# STM32F103.net
KiCad netlist of a schematic drawn in Altium Designer
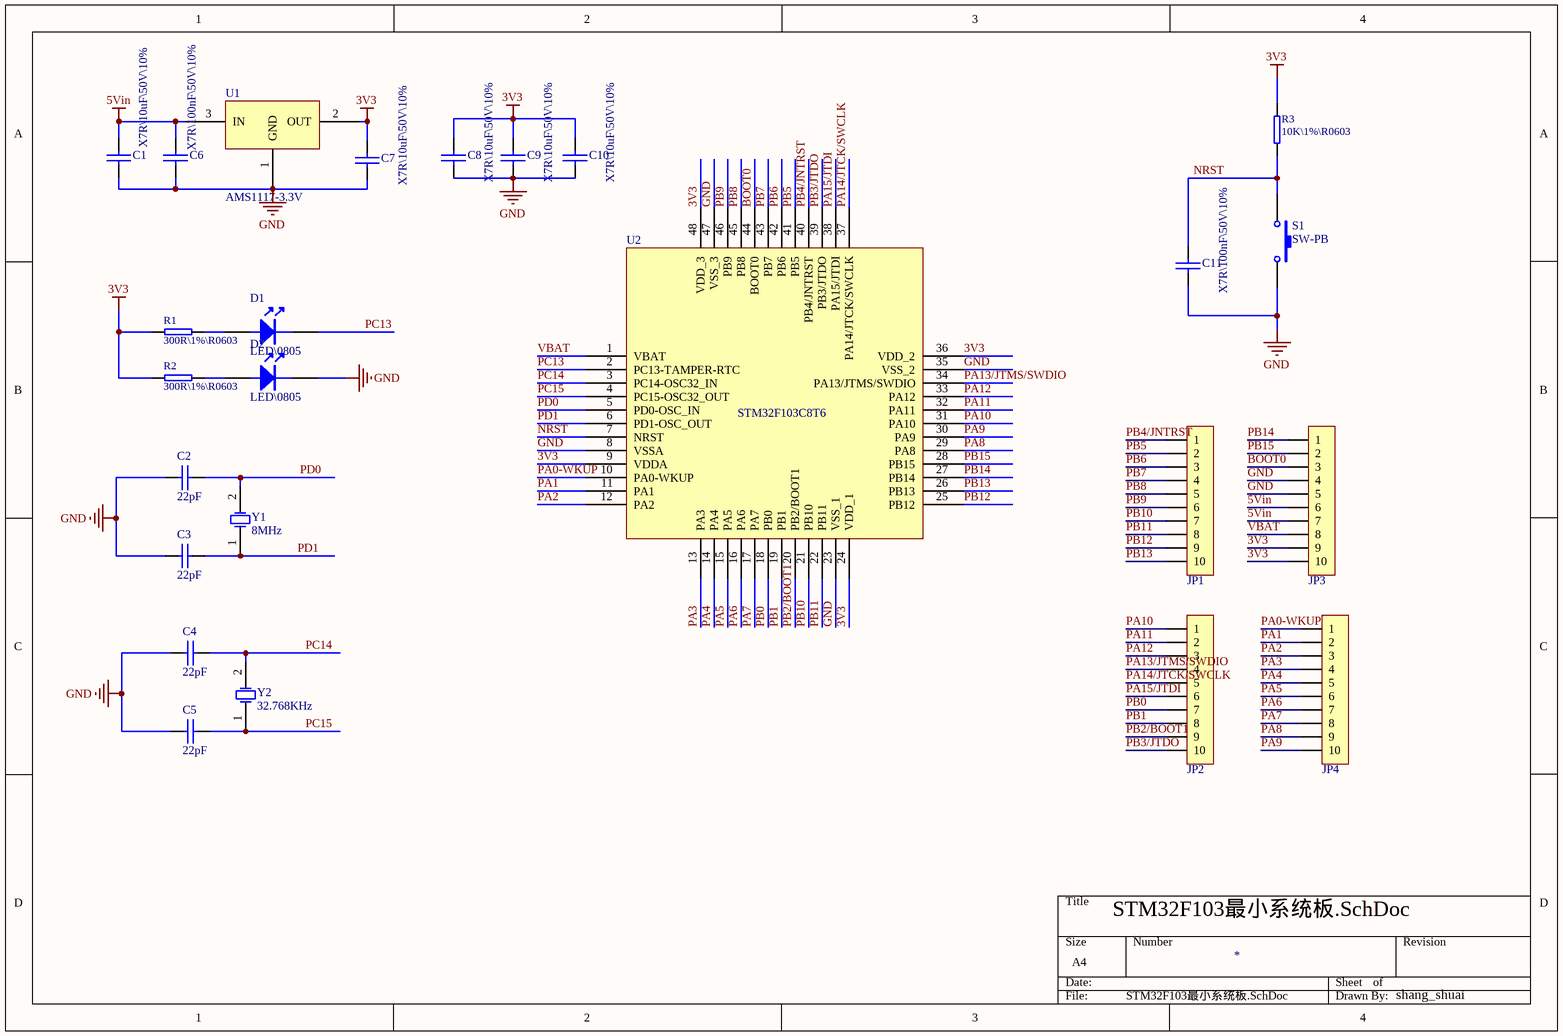
[diagram p0: STM32F103最小系统板.SchDoc]

(export (version "E")
  (design (tool "Eeschema 10.0.6"))
  (components
    (comp (ref "C1")
      (value "X7~{R}10u~{F}50~{V}10%")
      (footprint "C0603")
      (description "Capacitor")
      (libsource (lib "SSSCH") (part "C"))
    )
    (comp (ref "C2")
      (value "22pF")
      (footprint "C0603")
      (description "Capacitor")
      (libsource (lib "SSSCH") (part "C"))
    )
    (comp (ref "C3")
      (value "22pF")
      (footprint "C0603")
      (description "Capacitor")
      (libsource (lib "SSSCH") (part "C"))
    )
    (comp (ref "C4")
      (value "22pF")
      (footprint "C0603")
      (description "Capacitor")
      (libsource (lib "SSSCH") (part "C"))
    )
    (comp (ref "C5")
      (value "22pF")
      (footprint "C0603")
      (description "Capacitor")
      (libsource (lib "SSSCH") (part "C"))
    )
    (comp (ref "C6")
      (value "X7~{R}100n~{F}50~{V}10%")
      (footprint "C0603")
      (description "Capacitor")
      (libsource (lib "SSSCH") (part "C"))
    )
    (comp (ref "C7")
      (value "X7~{R}10u~{F}50~{V}10%")
      (footprint "C0603")
      (description "Capacitor")
      (libsource (lib "SSSCH") (part "C"))
    )
    (comp (ref "C8")
      (value "X7~{R}10u~{F}50~{V}10%")
      (footprint "C0603")
      (description "Capacitor")
      (libsource (lib "SSSCH") (part "C"))
    )
    (comp (ref "C9")
      (value "X7~{R}10u~{F}50~{V}10%")
      (footprint "C0603")
      (description "Capacitor")
      (libsource (lib "SSSCH") (part "C"))
    )
    (comp (ref "C10")
      (value "X7~{R}10u~{F}50~{V}10%")
      (footprint "C0603")
      (description "Capacitor")
      (libsource (lib "SSSCH") (part "C"))
    )
    (comp (ref "C11")
      (value "X7~{R}100n~{F}50~{V}10%")
      (footprint "C0603")
      (description "Capacitor")
      (libsource (lib "SSSCH") (part "C"))
    )
    (comp (ref "D1")
      (value "LE~{D}0805")
      (footprint "LED 0805R")
      (description "红色")
      (libsource (lib "SSSCH") (part "LED"))
    )
    (comp (ref "D2")
      (value "LE~{D}0805")
      (footprint "LED 0805R")
      (description "红色")
      (libsource (lib "SSSCH") (part "LED"))
    )
    (comp (ref "JP1")
      (value "HDR-1X10")
      (footprint "HDR2.54-LI-10P")
      (description "10P接插件")
      (fields (field (name "版权归属") "源创客"))
      (libsource (lib "4.5   - 接插件-脚距2.54") (part "Header 10"))
    )
    (comp (ref "JP2")
      (value "HDR-1X10")
      (footprint "HDR2.54-LI-10P")
      (description "10P接插件")
      (fields (field (name "版权归属") "源创客"))
      (libsource (lib "4.5   - 接插件-脚距2.54") (part "Header 10"))
    )
    (comp (ref "JP3")
      (value "HDR-1X10")
      (footprint "HDR2.54-LI-10P")
      (description "10P接插件")
      (fields (field (name "版权归属") "源创客"))
      (libsource (lib "4.5   - 接插件-脚距2.54") (part "Header 10"))
    )
    (comp (ref "JP4")
      (value "HDR-1X10")
      (footprint "HDR2.54-LI-10P")
      (description "10P接插件")
      (fields (field (name "版权归属") "源创客"))
      (libsource (lib "4.5   - 接插件-脚距2.54") (part "Header 10"))
    )
    (comp (ref "R1")
      (value "300~{R}1~{%}R0603")
      (footprint "R0603")
      (description "电阻")
      (libsource (lib "SSSCH") (part "R"))
    )
    (comp (ref "R2")
      (value "300~{R}1~{%}R0603")
      (footprint "R0603")
      (description "电阻")
      (libsource (lib "SSSCH") (part "R"))
    )
    (comp (ref "R3")
      (value "10~{K}1~{%}R0603")
      (footprint "R0603")
      (description "电阻")
      (libsource (lib "SSSCH") (part "R"))
    )
    (comp (ref "S1")
      (value "SW-PB")
      (footprint "TSW SMD-3*6*4.3")
      (description "Switch")
      (fields (field (name "PUBLISHER") "Altium Limited"))
      (libsource (lib "Miscellaneous Devices") (part "SW-PB"))
    )
    (comp (ref "U1")
      (value "AMS1117-3.3V")
      (footprint "SOT223_L")
      (libsource (lib "SSSCH") (part "AMS1117-3.3V"))
    )
    (comp (ref "U2")
      (value "STM32F103C8T6")
      (footprint "LQFP48-7*7")
      (description "48PIN")
      (libsource (lib "SSSCH") (part "STM32F103C8T6"))
    )
    (comp (ref "Y1")
      (value "8MHz")
      (footprint "OSC HC-49S")
      (description "2脚无源脚晶振")
      (fields (field (name "PUBLISHER") "Altium Limited"))
      (libsource (lib "Miscellaneous Devices") (part "XTAL"))
    )
    (comp (ref "Y2")
      (value "32.768KHz")
      (footprint "OSC-2x6-WI-B")
      (description "2脚无源脚晶振")
      (fields (field (name "PUBLISHER") "Altium Limited"))
      (libsource (lib "Miscellaneous Devices") (part "XTAL"))
    )
  )
  (nets
    (net (code "1") (name "/BOOT0") (class "Default")
      (node (ref "JP3") (pin "3") (pinfunction "3_3") (pintype "passive"))
      (node (ref "U2") (pin "44") (pinfunction "BOOT0_44") (pintype "passive"))
    )
    (net (code "2") (name "/NRST") (class "Default")
      (node (ref "C11") (pin "1") (pintype "passive"))
      (node (ref "R3") (pin "2") (pintype "passive"))
      (node (ref "S1") (pin "1") (pinfunction "1_1") (pintype "passive"))
      (node (ref "U2") (pin "7") (pinfunction "NRST_7") (pintype "passive"))
    )
    (net (code "3") (name "/PA0-WKUP") (class "Default")
      (node (ref "JP4") (pin "1") (pinfunction "1_1") (pintype "passive"))
      (node (ref "U2") (pin "10") (pinfunction "PA0-WKUP_10") (pintype "passive"))
    )
    (net (code "4") (name "/PA1") (class "Default")
      (node (ref "JP4") (pin "2") (pinfunction "2_2") (pintype "passive"))
      (node (ref "U2") (pin "11") (pinfunction "PA1_11") (pintype "passive"))
    )
    (net (code "5") (name "/PA2") (class "Default")
      (node (ref "JP4") (pin "3") (pinfunction "3_3") (pintype "passive"))
      (node (ref "U2") (pin "12") (pinfunction "PA2_12") (pintype "passive"))
    )
    (net (code "6") (name "/PA3") (class "Default")
      (node (ref "JP4") (pin "4") (pinfunction "4_4") (pintype "passive"))
      (node (ref "U2") (pin "13") (pinfunction "PA3_13") (pintype "passive"))
    )
    (net (code "7") (name "/PA4") (class "Default")
      (node (ref "JP4") (pin "5") (pinfunction "5_5") (pintype "passive"))
      (node (ref "U2") (pin "14") (pinfunction "PA4_14") (pintype "passive"))
    )
    (net (code "8") (name "/PA5") (class "Default")
      (node (ref "JP4") (pin "6") (pinfunction "6_6") (pintype "passive"))
      (node (ref "U2") (pin "15") (pinfunction "PA5_15") (pintype "passive"))
    )
    (net (code "9") (name "/PA6") (class "Default")
      (node (ref "JP4") (pin "7") (pinfunction "7_7") (pintype "passive"))
      (node (ref "U2") (pin "16") (pinfunction "PA6_16") (pintype "passive"))
    )
    (net (code "10") (name "/PA7") (class "Default")
      (node (ref "JP4") (pin "8") (pinfunction "8_8") (pintype "passive"))
      (node (ref "U2") (pin "17") (pinfunction "PA7_17") (pintype "passive"))
    )
    (net (code "11") (name "/PA8") (class "Default")
      (node (ref "JP4") (pin "9") (pinfunction "9_9") (pintype "passive"))
      (node (ref "U2") (pin "29") (pinfunction "PA8_29") (pintype "passive"))
    )
    (net (code "12") (name "/PA9") (class "Default")
      (node (ref "JP4") (pin "10") (pinfunction "10_10") (pintype "passive"))
      (node (ref "U2") (pin "30") (pinfunction "PA9_30") (pintype "passive"))
    )
    (net (code "13") (name "/PA10") (class "Default")
      (node (ref "JP2") (pin "1") (pinfunction "1_1") (pintype "passive"))
      (node (ref "U2") (pin "31") (pinfunction "PA10_31") (pintype "passive"))
    )
    (net (code "14") (name "/PA11") (class "Default")
      (node (ref "JP2") (pin "2") (pinfunction "2_2") (pintype "passive"))
      (node (ref "U2") (pin "32") (pinfunction "PA11_32") (pintype "passive"))
    )
    (net (code "15") (name "/PA12") (class "Default")
      (node (ref "JP2") (pin "3") (pinfunction "3_3") (pintype "passive"))
      (node (ref "U2") (pin "33") (pinfunction "PA12_33") (pintype "passive"))
    )
    (net (code "16") (name "/PA13{slash}JTMS{slash}SWDIO") (class "Default")
      (node (ref "JP2") (pin "4") (pinfunction "4_4") (pintype "passive"))
      (node (ref "U2") (pin "34") (pinfunction "PA13/JTMS/SWDIO_34") (pintype "passive"))
    )
    (net (code "17") (name "/PA14{slash}JTCK{slash}SWCLK") (class "Default")
      (node (ref "JP2") (pin "5") (pinfunction "5_5") (pintype "passive"))
      (node (ref "U2") (pin "37") (pinfunction "PA14/JTCK/SWCLK_37") (pintype "passive"))
    )
    (net (code "18") (name "/PA15{slash}JTDI") (class "Default")
      (node (ref "JP2") (pin "6") (pinfunction "6_6") (pintype "passive"))
      (node (ref "U2") (pin "38") (pinfunction "PA15/JTDI_38") (pintype "passive"))
    )
    (net (code "19") (name "/PB0") (class "Default")
      (node (ref "JP2") (pin "7") (pinfunction "7_7") (pintype "passive"))
      (node (ref "U2") (pin "18") (pinfunction "PB0_18") (pintype "passive"))
    )
    (net (code "20") (name "/PB1") (class "Default")
      (node (ref "JP2") (pin "8") (pinfunction "8_8") (pintype "passive"))
      (node (ref "U2") (pin "19") (pinfunction "PB1_19") (pintype "passive"))
    )
    (net (code "21") (name "/PB2{slash}BOOT1") (class "Default")
      (node (ref "JP2") (pin "9") (pinfunction "9_9") (pintype "passive"))
      (node (ref "U2") (pin "20") (pinfunction "PB2/BOOT1_20") (pintype "passive"))
    )
    (net (code "22") (name "/PB3{slash}JTDO") (class "Default")
      (node (ref "JP2") (pin "10") (pinfunction "10_10") (pintype "passive"))
      (node (ref "U2") (pin "39") (pinfunction "PB3/JTDO_39") (pintype "passive"))
    )
    (net (code "23") (name "/PB4{slash}JNTRST") (class "Default")
      (node (ref "JP1") (pin "1") (pinfunction "1_1") (pintype "passive"))
      (node (ref "U2") (pin "40") (pinfunction "PB4/JNTRST_40") (pintype "passive"))
    )
    (net (code "24") (name "/PB5") (class "Default")
      (node (ref "JP1") (pin "2") (pinfunction "2_2") (pintype "passive"))
      (node (ref "U2") (pin "41") (pinfunction "PB5_41") (pintype "passive"))
    )
    (net (code "25") (name "/PB6") (class "Default")
      (node (ref "JP1") (pin "3") (pinfunction "3_3") (pintype "passive"))
      (node (ref "U2") (pin "42") (pinfunction "PB6_42") (pintype "passive"))
    )
    (net (code "26") (name "/PB7") (class "Default")
      (node (ref "JP1") (pin "4") (pinfunction "4_4") (pintype "passive"))
      (node (ref "U2") (pin "43") (pinfunction "PB7_43") (pintype "passive"))
    )
    (net (code "27") (name "/PB8") (class "Default")
      (node (ref "JP1") (pin "5") (pinfunction "5_5") (pintype "passive"))
      (node (ref "U2") (pin "45") (pinfunction "PB8_45") (pintype "passive"))
    )
    (net (code "28") (name "/PB9") (class "Default")
      (node (ref "JP1") (pin "6") (pinfunction "6_6") (pintype "passive"))
      (node (ref "U2") (pin "46") (pinfunction "PB9_46") (pintype "passive"))
    )
    (net (code "29") (name "/PB10") (class "Default")
      (node (ref "JP1") (pin "7") (pinfunction "7_7") (pintype "passive"))
      (node (ref "U2") (pin "21") (pinfunction "PB10_21") (pintype "passive"))
    )
    (net (code "30") (name "/PB11") (class "Default")
      (node (ref "JP1") (pin "8") (pinfunction "8_8") (pintype "passive"))
      (node (ref "U2") (pin "22") (pinfunction "PB11_22") (pintype "passive"))
    )
    (net (code "31") (name "/PB12") (class "Default")
      (node (ref "JP1") (pin "9") (pinfunction "9_9") (pintype "passive"))
      (node (ref "U2") (pin "25") (pinfunction "PB12_25") (pintype "passive"))
    )
    (net (code "32") (name "/PB13") (class "Default")
      (node (ref "JP1") (pin "10") (pinfunction "10_10") (pintype "passive"))
      (node (ref "U2") (pin "26") (pinfunction "PB13_26") (pintype "passive"))
    )
    (net (code "33") (name "/PB14") (class "Default")
      (node (ref "JP3") (pin "1") (pinfunction "1_1") (pintype "passive"))
      (node (ref "U2") (pin "27") (pinfunction "PB14_27") (pintype "passive"))
    )
    (net (code "34") (name "/PB15") (class "Default")
      (node (ref "JP3") (pin "2") (pinfunction "2_2") (pintype "passive"))
      (node (ref "U2") (pin "28") (pinfunction "PB15_28") (pintype "passive"))
    )
    (net (code "35") (name "/PC13") (class "Default")
      (node (ref "D1") (pin "2") (pinfunction "2_2") (pintype "passive"))
      (node (ref "U2") (pin "2") (pinfunction "PC13-TAMPER-RTC_2") (pintype "passive"))
    )
    (net (code "36") (name "/PC14") (class "Default")
      (node (ref "C4") (pin "2") (pintype "passive"))
      (node (ref "U2") (pin "3") (pinfunction "PC14-OSC32_IN_3") (pintype "passive"))
      (node (ref "Y2") (pin "2") (pinfunction "OSC2_2") (pintype "passive"))
    )
    (net (code "37") (name "/PC15") (class "Default")
      (node (ref "C5") (pin "2") (pintype "passive"))
      (node (ref "U2") (pin "4") (pinfunction "PC15-OSC32_OUT_4") (pintype "passive"))
      (node (ref "Y2") (pin "1") (pinfunction "OSC1_1") (pintype "passive"))
    )
    (net (code "38") (name "/PD0") (class "Default")
      (node (ref "C2") (pin "2") (pintype "passive"))
      (node (ref "U2") (pin "5") (pinfunction "PD0-OSC_IN_5") (pintype "passive"))
      (node (ref "Y1") (pin "2") (pinfunction "OSC2_2") (pintype "passive"))
    )
    (net (code "39") (name "/PD1") (class "Default")
      (node (ref "C3") (pin "2") (pintype "passive"))
      (node (ref "U2") (pin "6") (pinfunction "PD1-OSC_OUT_6") (pintype "passive"))
      (node (ref "Y1") (pin "1") (pinfunction "OSC1_1") (pintype "passive"))
    )
    (net (code "40") (name "/VBAT") (class "Default")
      (node (ref "JP3") (pin "8") (pinfunction "8_8") (pintype "passive"))
      (node (ref "U2") (pin "1") (pinfunction "VBAT_1") (pintype "passive"))
    )
    (net (code "41") (name "3V3") (class "Default")
      (node (ref "C10") (pin "1") (pintype "passive"))
      (node (ref "C7") (pin "1") (pintype "passive"))
      (node (ref "C8") (pin "1") (pintype "passive"))
      (node (ref "C9") (pin "1") (pintype "passive"))
      (node (ref "JP3") (pin "10") (pinfunction "10_10") (pintype "passive"))
      (node (ref "JP3") (pin "9") (pinfunction "9_9") (pintype "passive"))
      (node (ref "R1") (pin "2") (pintype "passive"))
      (node (ref "R2") (pin "2") (pintype "passive"))
      (node (ref "R3") (pin "1") (pintype "passive"))
      (node (ref "U1") (pin "2") (pinfunction "OUT_2") (pintype "passive"))
      (node (ref "U2") (pin "24") (pinfunction "VDD_1_24") (pintype "passive"))
      (node (ref "U2") (pin "36") (pinfunction "VDD_2_36") (pintype "passive"))
      (node (ref "U2") (pin "48") (pinfunction "VDD_3_48") (pintype "passive"))
      (node (ref "U2") (pin "9") (pinfunction "VDDA_9") (pintype "passive"))
    )
    (net (code "42") (name "5Vin") (class "Default")
      (node (ref "C1") (pin "1") (pintype "passive"))
      (node (ref "C6") (pin "1") (pintype "passive"))
      (node (ref "JP3") (pin "6") (pinfunction "6_6") (pintype "passive"))
      (node (ref "JP3") (pin "7") (pinfunction "7_7") (pintype "passive"))
      (node (ref "U1") (pin "3") (pinfunction "IN_3") (pintype "passive"))
    )
    (net (code "43") (name "GND") (class "Default")
      (node (ref "C1") (pin "2") (pintype "passive"))
      (node (ref "C10") (pin "2") (pintype "passive"))
      (node (ref "C11") (pin "2") (pintype "passive"))
      (node (ref "C2") (pin "1") (pintype "passive"))
      (node (ref "C3") (pin "1") (pintype "passive"))
      (node (ref "C4") (pin "1") (pintype "passive"))
      (node (ref "C5") (pin "1") (pintype "passive"))
      (node (ref "C6") (pin "2") (pintype "passive"))
      (node (ref "C7") (pin "2") (pintype "passive"))
      (node (ref "C8") (pin "2") (pintype "passive"))
      (node (ref "C9") (pin "2") (pintype "passive"))
      (node (ref "D2") (pin "2") (pinfunction "2_2") (pintype "passive"))
      (node (ref "JP3") (pin "4") (pinfunction "4_4") (pintype "passive"))
      (node (ref "JP3") (pin "5") (pinfunction "5_5") (pintype "passive"))
      (node (ref "S1") (pin "2") (pinfunction "2_2") (pintype "passive"))
      (node (ref "U1") (pin "1") (pinfunction "GND_1") (pintype "passive"))
      (node (ref "U2") (pin "23") (pinfunction "VSS_1_23") (pintype "passive"))
      (node (ref "U2") (pin "35") (pinfunction "VSS_2_35") (pintype "passive"))
      (node (ref "U2") (pin "47") (pinfunction "VSS_3_47") (pintype "passive"))
      (node (ref "U2") (pin "8") (pinfunction "VSSA_8") (pintype "passive"))
    )
    (net (code "44") (name "Net-(D1-Pad1)") (class "Default")
      (node (ref "D1") (pin "1") (pinfunction "1_1") (pintype "passive"))
      (node (ref "R1") (pin "1") (pintype "passive"))
    )
    (net (code "45") (name "Net-(D2-Pad1)") (class "Default")
      (node (ref "D2") (pin "1") (pinfunction "1_1") (pintype "passive"))
      (node (ref "R2") (pin "1") (pintype "passive"))
    )
  )
)
